# r.net
KiCad netlist of a schematic drawn in EAGLE
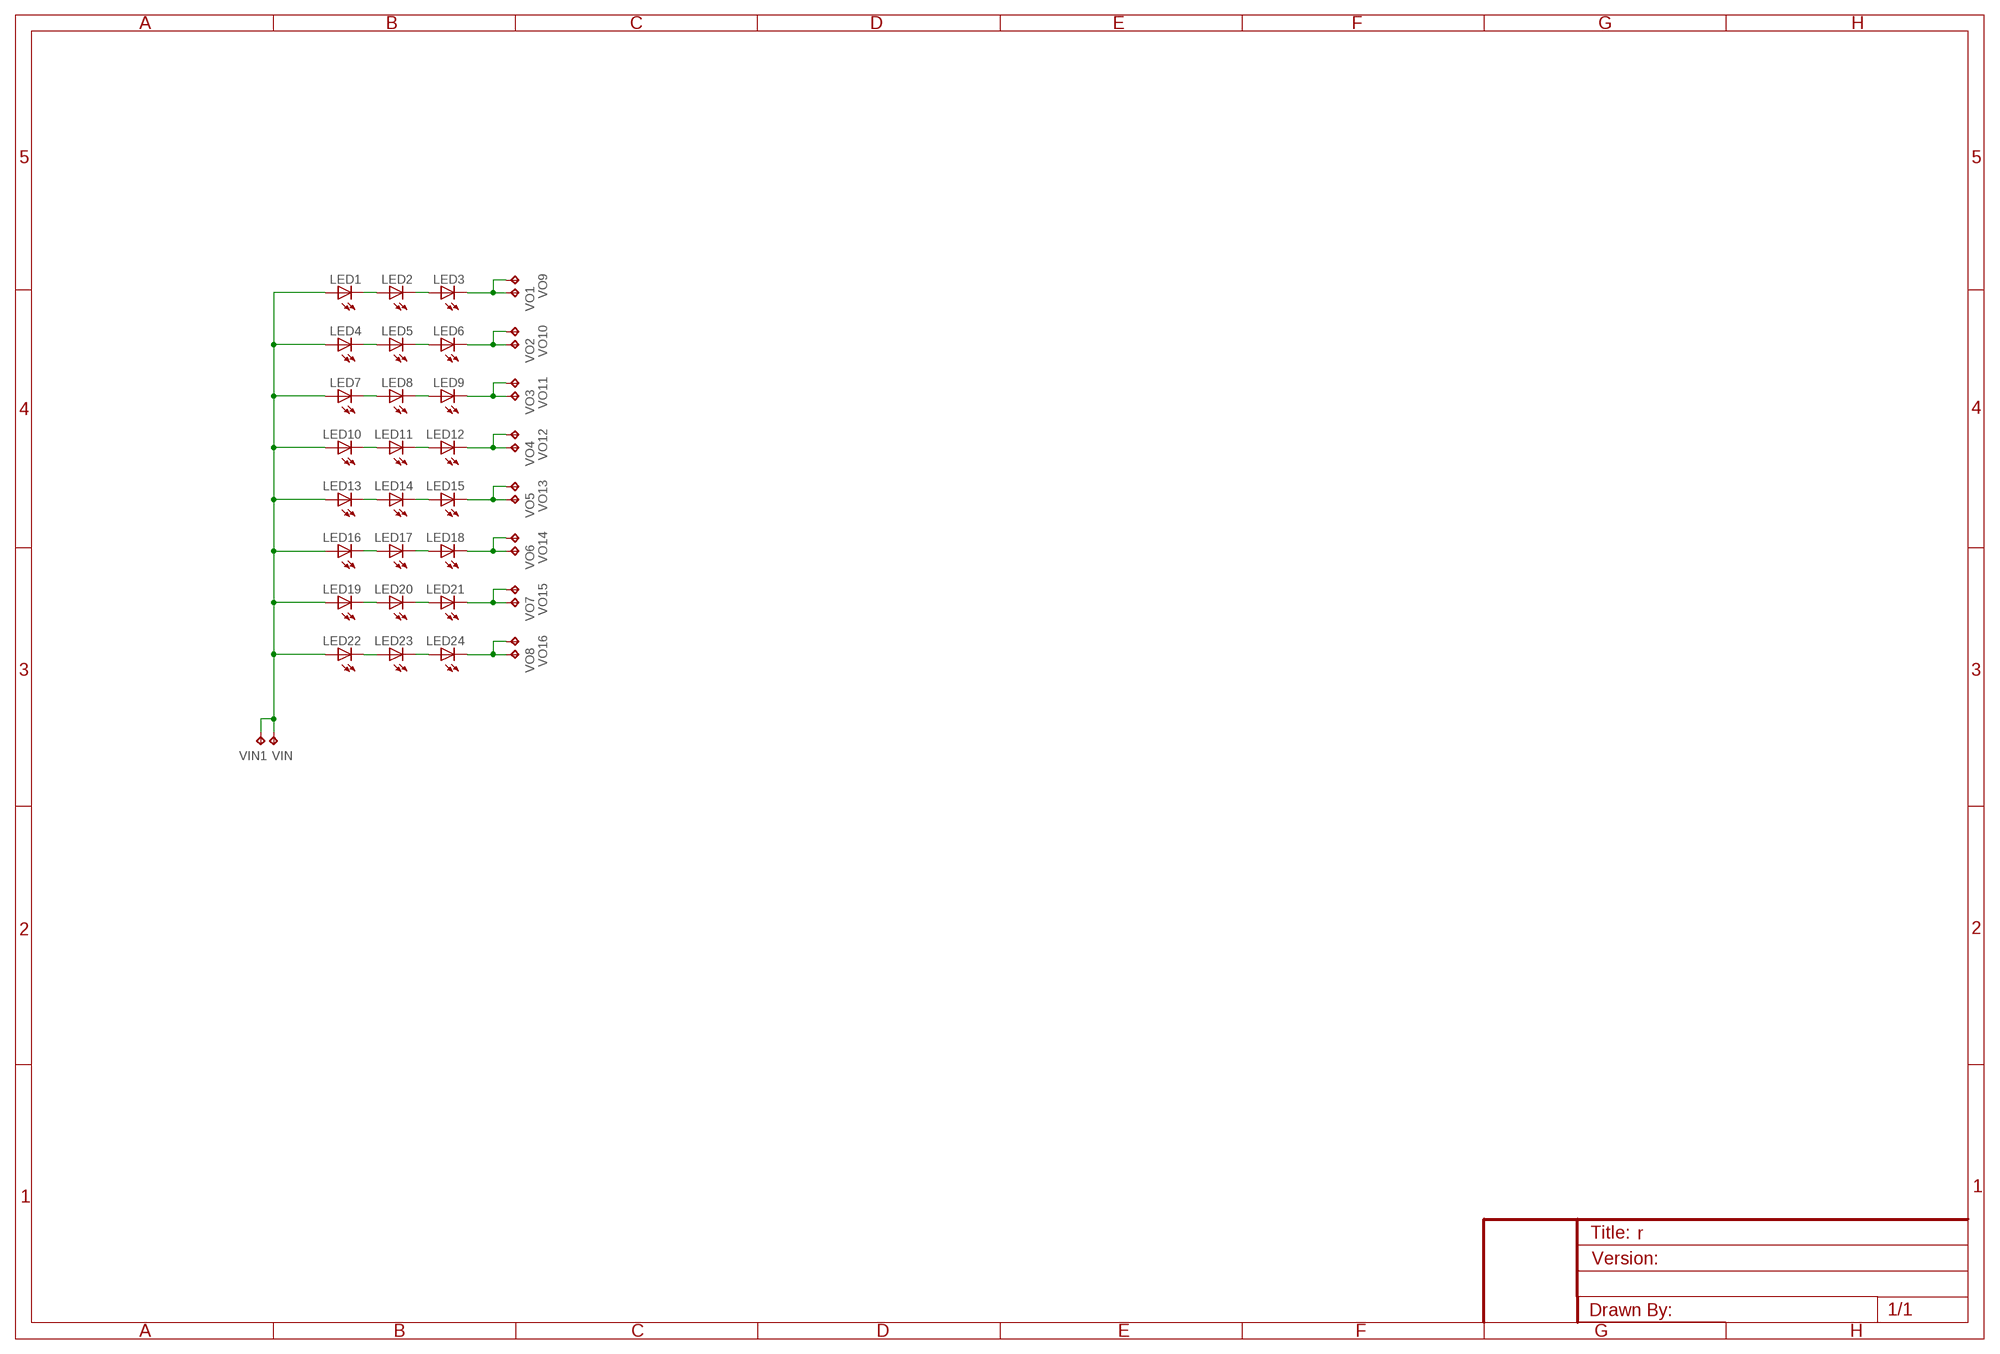
[diagram p0: schematic, sheet 1]

(export (version "E")
  (design (tool "Eeschema 10.0.6"))
  (components
    (comp (ref "LED1")
      (value "LED0805")
      (footprint "eagle-import:LED_0805")
      (libsource (lib "eagle-import") (part "LED0805"))
    )
    (comp (ref "LED2")
      (value "LED0805")
      (footprint "eagle-import:LED_0805")
      (libsource (lib "eagle-import") (part "LED0805"))
    )
    (comp (ref "LED3")
      (value "LED0805")
      (footprint "eagle-import:LED_0805")
      (libsource (lib "eagle-import") (part "LED0805"))
    )
    (comp (ref "LED4")
      (value "LED0805")
      (footprint "eagle-import:LED_0805")
      (libsource (lib "eagle-import") (part "LED0805"))
    )
    (comp (ref "LED5")
      (value "LED0805")
      (footprint "eagle-import:LED_0805")
      (libsource (lib "eagle-import") (part "LED0805"))
    )
    (comp (ref "LED6")
      (value "LED0805")
      (footprint "eagle-import:LED_0805")
      (libsource (lib "eagle-import") (part "LED0805"))
    )
    (comp (ref "LED7")
      (value "LED0805")
      (footprint "eagle-import:LED_0805")
      (libsource (lib "eagle-import") (part "LED0805"))
    )
    (comp (ref "LED8")
      (value "LED0805")
      (footprint "eagle-import:LED_0805")
      (libsource (lib "eagle-import") (part "LED0805"))
    )
    (comp (ref "LED9")
      (value "LED0805")
      (footprint "eagle-import:LED_0805")
      (libsource (lib "eagle-import") (part "LED0805"))
    )
    (comp (ref "LED10")
      (value "LED0805")
      (footprint "eagle-import:LED_0805")
      (libsource (lib "eagle-import") (part "LED0805"))
    )
    (comp (ref "LED11")
      (value "LED0805")
      (footprint "eagle-import:LED_0805")
      (libsource (lib "eagle-import") (part "LED0805"))
    )
    (comp (ref "LED12")
      (value "LED0805")
      (footprint "eagle-import:LED_0805")
      (libsource (lib "eagle-import") (part "LED0805"))
    )
    (comp (ref "LED13")
      (value "LED0805")
      (footprint "eagle-import:LED_0805")
      (libsource (lib "eagle-import") (part "LED0805"))
    )
    (comp (ref "LED14")
      (value "LED0805")
      (footprint "eagle-import:LED_0805")
      (libsource (lib "eagle-import") (part "LED0805"))
    )
    (comp (ref "LED15")
      (value "LED0805")
      (footprint "eagle-import:LED_0805")
      (libsource (lib "eagle-import") (part "LED0805"))
    )
    (comp (ref "LED16")
      (value "LED0805")
      (footprint "eagle-import:LED_0805")
      (libsource (lib "eagle-import") (part "LED0805"))
    )
    (comp (ref "LED17")
      (value "LED0805")
      (footprint "eagle-import:LED_0805")
      (libsource (lib "eagle-import") (part "LED0805"))
    )
    (comp (ref "LED18")
      (value "LED0805")
      (footprint "eagle-import:LED_0805")
      (libsource (lib "eagle-import") (part "LED0805"))
    )
    (comp (ref "LED19")
      (value "LED0805")
      (footprint "eagle-import:LED_0805")
      (libsource (lib "eagle-import") (part "LED0805"))
    )
    (comp (ref "LED20")
      (value "LED0805")
      (footprint "eagle-import:LED_0805")
      (libsource (lib "eagle-import") (part "LED0805"))
    )
    (comp (ref "LED21")
      (value "LED0805")
      (footprint "eagle-import:LED_0805")
      (libsource (lib "eagle-import") (part "LED0805"))
    )
    (comp (ref "LED22")
      (value "LED0805")
      (footprint "eagle-import:LED_0805")
      (libsource (lib "eagle-import") (part "LED0805"))
    )
    (comp (ref "LED23")
      (value "LED0805")
      (footprint "eagle-import:LED_0805")
      (libsource (lib "eagle-import") (part "LED0805"))
    )
    (comp (ref "LED24")
      (value "LED0805")
      (footprint "eagle-import:LED_0805")
      (libsource (lib "eagle-import") (part "LED0805"))
    )
    (comp (ref "VIN")
      (value "TEST_POINTPAD1-20")
      (footprint "eagle-import:P1-20")
      (libsource (lib "eagle-import") (part "TEST_POINTPAD1-20"))
    )
    (comp (ref "VIN1")
      (value "TEST_POINTPAD1-20")
      (footprint "eagle-import:P1-20")
      (libsource (lib "eagle-import") (part "TEST_POINTPAD1-20"))
    )
    (comp (ref "VO1")
      (value "TEST_POINTPAD1-20")
      (footprint "eagle-import:P1-20")
      (libsource (lib "eagle-import") (part "TEST_POINTPAD1-20"))
    )
    (comp (ref "VO2")
      (value "TEST_POINTPAD1-20")
      (footprint "eagle-import:P1-20")
      (libsource (lib "eagle-import") (part "TEST_POINTPAD1-20"))
    )
    (comp (ref "VO3")
      (value "TEST_POINTPAD1-20")
      (footprint "eagle-import:P1-20")
      (libsource (lib "eagle-import") (part "TEST_POINTPAD1-20"))
    )
    (comp (ref "VO4")
      (value "TEST_POINTPAD1-20")
      (footprint "eagle-import:P1-20")
      (libsource (lib "eagle-import") (part "TEST_POINTPAD1-20"))
    )
    (comp (ref "VO5")
      (value "TEST_POINTPAD1-20")
      (footprint "eagle-import:P1-20")
      (libsource (lib "eagle-import") (part "TEST_POINTPAD1-20"))
    )
    (comp (ref "VO6")
      (value "TEST_POINTPAD1-20")
      (footprint "eagle-import:P1-20")
      (libsource (lib "eagle-import") (part "TEST_POINTPAD1-20"))
    )
    (comp (ref "VO7")
      (value "TEST_POINTPAD1-20")
      (footprint "eagle-import:P1-20")
      (libsource (lib "eagle-import") (part "TEST_POINTPAD1-20"))
    )
    (comp (ref "VO8")
      (value "TEST_POINTPAD1-20")
      (footprint "eagle-import:P1-20")
      (libsource (lib "eagle-import") (part "TEST_POINTPAD1-20"))
    )
    (comp (ref "VO9")
      (value "TEST_POINTPAD1-20")
      (footprint "eagle-import:P1-20")
      (libsource (lib "eagle-import") (part "TEST_POINTPAD1-20"))
    )
    (comp (ref "VO10")
      (value "TEST_POINTPAD1-20")
      (footprint "eagle-import:P1-20")
      (libsource (lib "eagle-import") (part "TEST_POINTPAD1-20"))
    )
    (comp (ref "VO11")
      (value "TEST_POINTPAD1-20")
      (footprint "eagle-import:P1-20")
      (libsource (lib "eagle-import") (part "TEST_POINTPAD1-20"))
    )
    (comp (ref "VO12")
      (value "TEST_POINTPAD1-20")
      (footprint "eagle-import:P1-20")
      (libsource (lib "eagle-import") (part "TEST_POINTPAD1-20"))
    )
    (comp (ref "VO13")
      (value "TEST_POINTPAD1-20")
      (footprint "eagle-import:P1-20")
      (libsource (lib "eagle-import") (part "TEST_POINTPAD1-20"))
    )
    (comp (ref "VO14")
      (value "TEST_POINTPAD1-20")
      (footprint "eagle-import:P1-20")
      (libsource (lib "eagle-import") (part "TEST_POINTPAD1-20"))
    )
    (comp (ref "VO15")
      (value "TEST_POINTPAD1-20")
      (footprint "eagle-import:P1-20")
      (libsource (lib "eagle-import") (part "TEST_POINTPAD1-20"))
    )
    (comp (ref "VO16")
      (value "TEST_POINTPAD1-20")
      (footprint "eagle-import:P1-20")
      (libsource (lib "eagle-import") (part "TEST_POINTPAD1-20"))
    )
  )
  (nets
    (net (code "1") (name "Net-(LED1-PadA)") (class "Default")
      (node (ref "LED1") (pin "A") (pinfunction "A_A") (pintype "passive"))
      (node (ref "LED10") (pin "A") (pinfunction "A_A") (pintype "passive"))
      (node (ref "LED13") (pin "A") (pinfunction "A_A") (pintype "passive"))
      (node (ref "LED16") (pin "A") (pinfunction "A_A") (pintype "passive"))
      (node (ref "LED19") (pin "A") (pinfunction "A_A") (pintype "passive"))
      (node (ref "LED22") (pin "A") (pinfunction "A_A") (pintype "passive"))
      (node (ref "LED4") (pin "A") (pinfunction "A_A") (pintype "passive"))
      (node (ref "LED7") (pin "A") (pinfunction "A_A") (pintype "passive"))
      (node (ref "VIN") (pin "TP") (pinfunction "TP_TP") (pintype "input"))
      (node (ref "VIN1") (pin "TP") (pinfunction "TP_TP") (pintype "input"))
    )
    (net (code "2") (name "Net-(LED1-PadC)") (class "Default")
      (node (ref "LED1") (pin "C") (pinfunction "C_C") (pintype "passive"))
      (node (ref "LED2") (pin "A") (pinfunction "A_A") (pintype "passive"))
    )
    (net (code "3") (name "Net-(LED2-PadC)") (class "Default")
      (node (ref "LED2") (pin "C") (pinfunction "C_C") (pintype "passive"))
      (node (ref "LED3") (pin "A") (pinfunction "A_A") (pintype "passive"))
    )
    (net (code "4") (name "Net-(LED3-PadC)") (class "Default")
      (node (ref "LED3") (pin "C") (pinfunction "C_C") (pintype "passive"))
      (node (ref "VO1") (pin "TP") (pinfunction "TP_TP") (pintype "input"))
      (node (ref "VO9") (pin "TP") (pinfunction "TP_TP") (pintype "input"))
    )
    (net (code "5") (name "Net-(LED4-PadC)") (class "Default")
      (node (ref "LED4") (pin "C") (pinfunction "C_C") (pintype "passive"))
      (node (ref "LED5") (pin "A") (pinfunction "A_A") (pintype "passive"))
    )
    (net (code "6") (name "Net-(LED5-PadC)") (class "Default")
      (node (ref "LED5") (pin "C") (pinfunction "C_C") (pintype "passive"))
      (node (ref "LED6") (pin "A") (pinfunction "A_A") (pintype "passive"))
    )
    (net (code "7") (name "Net-(LED6-PadC)") (class "Default")
      (node (ref "LED6") (pin "C") (pinfunction "C_C") (pintype "passive"))
      (node (ref "VO10") (pin "TP") (pinfunction "TP_TP") (pintype "input"))
      (node (ref "VO2") (pin "TP") (pinfunction "TP_TP") (pintype "input"))
    )
    (net (code "8") (name "Net-(LED7-PadC)") (class "Default")
      (node (ref "LED7") (pin "C") (pinfunction "C_C") (pintype "passive"))
      (node (ref "LED8") (pin "A") (pinfunction "A_A") (pintype "passive"))
    )
    (net (code "9") (name "Net-(LED8-PadC)") (class "Default")
      (node (ref "LED8") (pin "C") (pinfunction "C_C") (pintype "passive"))
      (node (ref "LED9") (pin "A") (pinfunction "A_A") (pintype "passive"))
    )
    (net (code "10") (name "Net-(LED9-PadC)") (class "Default")
      (node (ref "LED9") (pin "C") (pinfunction "C_C") (pintype "passive"))
      (node (ref "VO11") (pin "TP") (pinfunction "TP_TP") (pintype "input"))
      (node (ref "VO3") (pin "TP") (pinfunction "TP_TP") (pintype "input"))
    )
    (net (code "11") (name "Net-(LED10-PadC)") (class "Default")
      (node (ref "LED10") (pin "C") (pinfunction "C_C") (pintype "passive"))
      (node (ref "LED11") (pin "A") (pinfunction "A_A") (pintype "passive"))
    )
    (net (code "12") (name "Net-(LED11-PadC)") (class "Default")
      (node (ref "LED11") (pin "C") (pinfunction "C_C") (pintype "passive"))
      (node (ref "LED12") (pin "A") (pinfunction "A_A") (pintype "passive"))
    )
    (net (code "13") (name "Net-(LED12-PadC)") (class "Default")
      (node (ref "LED12") (pin "C") (pinfunction "C_C") (pintype "passive"))
      (node (ref "VO12") (pin "TP") (pinfunction "TP_TP") (pintype "input"))
      (node (ref "VO4") (pin "TP") (pinfunction "TP_TP") (pintype "input"))
    )
    (net (code "14") (name "Net-(LED13-PadC)") (class "Default")
      (node (ref "LED13") (pin "C") (pinfunction "C_C") (pintype "passive"))
      (node (ref "LED14") (pin "A") (pinfunction "A_A") (pintype "passive"))
    )
    (net (code "15") (name "Net-(LED14-PadC)") (class "Default")
      (node (ref "LED14") (pin "C") (pinfunction "C_C") (pintype "passive"))
      (node (ref "LED15") (pin "A") (pinfunction "A_A") (pintype "passive"))
    )
    (net (code "16") (name "Net-(LED15-PadC)") (class "Default")
      (node (ref "LED15") (pin "C") (pinfunction "C_C") (pintype "passive"))
      (node (ref "VO13") (pin "TP") (pinfunction "TP_TP") (pintype "input"))
      (node (ref "VO5") (pin "TP") (pinfunction "TP_TP") (pintype "input"))
    )
    (net (code "17") (name "Net-(LED16-PadC)") (class "Default")
      (node (ref "LED16") (pin "C") (pinfunction "C_C") (pintype "passive"))
      (node (ref "LED17") (pin "A") (pinfunction "A_A") (pintype "passive"))
    )
    (net (code "18") (name "Net-(LED17-PadC)") (class "Default")
      (node (ref "LED17") (pin "C") (pinfunction "C_C") (pintype "passive"))
      (node (ref "LED18") (pin "A") (pinfunction "A_A") (pintype "passive"))
    )
    (net (code "19") (name "Net-(LED18-PadC)") (class "Default")
      (node (ref "LED18") (pin "C") (pinfunction "C_C") (pintype "passive"))
      (node (ref "VO14") (pin "TP") (pinfunction "TP_TP") (pintype "input"))
      (node (ref "VO6") (pin "TP") (pinfunction "TP_TP") (pintype "input"))
    )
    (net (code "20") (name "Net-(LED19-PadC)") (class "Default")
      (node (ref "LED19") (pin "C") (pinfunction "C_C") (pintype "passive"))
      (node (ref "LED20") (pin "A") (pinfunction "A_A") (pintype "passive"))
    )
    (net (code "21") (name "Net-(LED20-PadC)") (class "Default")
      (node (ref "LED20") (pin "C") (pinfunction "C_C") (pintype "passive"))
      (node (ref "LED21") (pin "A") (pinfunction "A_A") (pintype "passive"))
    )
    (net (code "22") (name "Net-(LED21-PadC)") (class "Default")
      (node (ref "LED21") (pin "C") (pinfunction "C_C") (pintype "passive"))
      (node (ref "VO15") (pin "TP") (pinfunction "TP_TP") (pintype "input"))
      (node (ref "VO7") (pin "TP") (pinfunction "TP_TP") (pintype "input"))
    )
    (net (code "23") (name "Net-(LED22-PadC)") (class "Default")
      (node (ref "LED22") (pin "C") (pinfunction "C_C") (pintype "passive"))
      (node (ref "LED23") (pin "A") (pinfunction "A_A") (pintype "passive"))
    )
    (net (code "24") (name "Net-(LED23-PadC)") (class "Default")
      (node (ref "LED23") (pin "C") (pinfunction "C_C") (pintype "passive"))
      (node (ref "LED24") (pin "A") (pinfunction "A_A") (pintype "passive"))
    )
    (net (code "25") (name "Net-(LED24-PadC)") (class "Default")
      (node (ref "LED24") (pin "C") (pinfunction "C_C") (pintype "passive"))
      (node (ref "VO16") (pin "TP") (pinfunction "TP_TP") (pintype "input"))
      (node (ref "VO8") (pin "TP") (pinfunction "TP_TP") (pintype "input"))
    )
  )
)
